# XOR.net
KiCad netlist of a schematic drawn in EAGLE
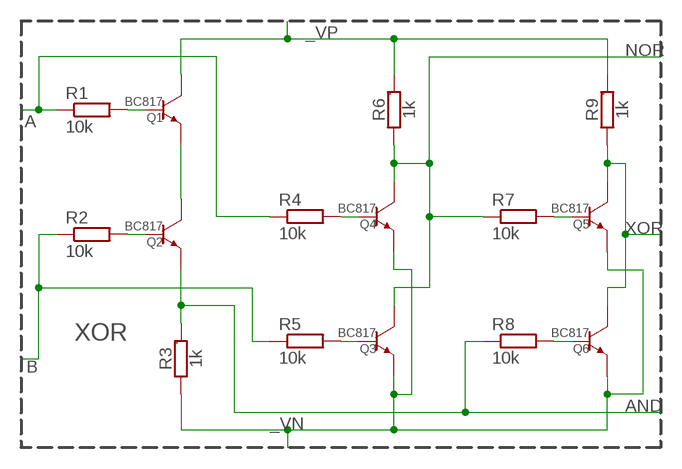
[diagram p0: schematic, sheet 1]

(export (version "E")
  (design (tool "Eeschema 10.0.6"))
  (components
    (comp (ref "Q1")
      (value "BC817")
      (footprint "eagle-import:SOT23")
      (libsource (lib "eagle-import") (part "TRANSISTOR-NPN-GENERIC-SOT23-BECDEFAULT"))
    )
    (comp (ref "Q2")
      (value "BC817")
      (footprint "eagle-import:SOT23")
      (libsource (lib "eagle-import") (part "TRANSISTOR-NPN-GENERIC-SOT23-BECDEFAULT"))
    )
    (comp (ref "Q3")
      (value "BC817")
      (footprint "eagle-import:SOT23")
      (libsource (lib "eagle-import") (part "TRANSISTOR-NPN-GENERIC-SOT23-BECDEFAULT"))
    )
    (comp (ref "Q4")
      (value "BC817")
      (footprint "eagle-import:SOT23")
      (libsource (lib "eagle-import") (part "TRANSISTOR-NPN-GENERIC-SOT23-BECDEFAULT"))
    )
    (comp (ref "Q5")
      (value "BC817")
      (footprint "eagle-import:SOT23")
      (libsource (lib "eagle-import") (part "TRANSISTOR-NPN-GENERIC-SOT23-BECDEFAULT"))
    )
    (comp (ref "Q6")
      (value "BC817")
      (footprint "eagle-import:SOT23")
      (libsource (lib "eagle-import") (part "TRANSISTOR-NPN-GENERIC-SOT23-BECDEFAULT"))
    )
    (comp (ref "R1")
      (value "10k")
      (footprint "eagle-import:R0603")
      (libsource (lib "eagle-import") (part "R-EU_R0603"))
    )
    (comp (ref "R2")
      (value "10k")
      (footprint "eagle-import:R0603")
      (libsource (lib "eagle-import") (part "R-EU_R0603"))
    )
    (comp (ref "R3")
      (value "1k")
      (footprint "eagle-import:R0603-MARK")
      (libsource (lib "eagle-import") (part "R-EU-MARKEDR0603"))
    )
    (comp (ref "R4")
      (value "10k")
      (footprint "eagle-import:R0603")
      (libsource (lib "eagle-import") (part "R-EU_R0603"))
    )
    (comp (ref "R5")
      (value "10k")
      (footprint "eagle-import:R0603")
      (libsource (lib "eagle-import") (part "R-EU_R0603"))
    )
    (comp (ref "R6")
      (value "1k")
      (footprint "eagle-import:R0603-MARK")
      (libsource (lib "eagle-import") (part "R-EU-MARKEDR0603"))
    )
    (comp (ref "R7")
      (value "10k")
      (footprint "eagle-import:R0603")
      (libsource (lib "eagle-import") (part "R-EU_R0603"))
    )
    (comp (ref "R8")
      (value "10k")
      (footprint "eagle-import:R0603")
      (libsource (lib "eagle-import") (part "R-EU_R0603"))
    )
    (comp (ref "R9")
      (value "1k")
      (footprint "eagle-import:R0603-MARK")
      (libsource (lib "eagle-import") (part "R-EU-MARKEDR0603"))
    )
  )
  (nets
    (net (code "1") (name "/A") (class "Default")
      (node (ref "R1") (pin "1") (pinfunction "1_1") (pintype "passive"))
      (node (ref "R4") (pin "1") (pinfunction "1_1") (pintype "passive"))
    )
    (net (code "2") (name "/AND") (class "Default")
      (node (ref "Q2") (pin "P$2") (pinfunction "EMITTER_P$2") (pintype "bidirectional"))
      (node (ref "R3") (pin "2") (pinfunction "2_2") (pintype "passive"))
      (node (ref "R8") (pin "1") (pinfunction "1_1") (pintype "passive"))
    )
    (net (code "3") (name "/B") (class "Default")
      (node (ref "R2") (pin "1") (pinfunction "1_1") (pintype "passive"))
      (node (ref "R5") (pin "1") (pinfunction "1_1") (pintype "passive"))
    )
    (net (code "4") (name "/NOR") (class "Default")
      (node (ref "Q3") (pin "P$3") (pinfunction "COLLECTOR_P$3") (pintype "bidirectional"))
      (node (ref "Q4") (pin "P$3") (pinfunction "COLLECTOR_P$3") (pintype "bidirectional"))
      (node (ref "R6") (pin "1") (pinfunction "1_1") (pintype "passive"))
      (node (ref "R7") (pin "1") (pinfunction "1_1") (pintype "passive"))
    )
    (net (code "5") (name "/XOR") (class "Default")
      (node (ref "Q5") (pin "P$3") (pinfunction "COLLECTOR_P$3") (pintype "bidirectional"))
      (node (ref "Q6") (pin "P$3") (pinfunction "COLLECTOR_P$3") (pintype "bidirectional"))
      (node (ref "R9") (pin "1") (pinfunction "1_1") (pintype "passive"))
    )
    (net (code "6") (name "/_VN") (class "Default")
      (node (ref "Q3") (pin "P$2") (pinfunction "EMITTER_P$2") (pintype "bidirectional"))
      (node (ref "Q4") (pin "P$2") (pinfunction "EMITTER_P$2") (pintype "bidirectional"))
      (node (ref "Q5") (pin "P$2") (pinfunction "EMITTER_P$2") (pintype "bidirectional"))
      (node (ref "Q6") (pin "P$2") (pinfunction "EMITTER_P$2") (pintype "bidirectional"))
      (node (ref "R3") (pin "1") (pinfunction "1_1") (pintype "passive"))
    )
    (net (code "7") (name "/_VP") (class "Default")
      (node (ref "Q1") (pin "P$3") (pinfunction "COLLECTOR_P$3") (pintype "bidirectional"))
      (node (ref "R6") (pin "2") (pinfunction "2_2") (pintype "passive"))
      (node (ref "R9") (pin "2") (pinfunction "2_2") (pintype "passive"))
    )
    (net (code "8") (name "Net-(Q1-BASE)") (class "Default")
      (node (ref "Q1") (pin "P$1") (pinfunction "BASE_P$1") (pintype "bidirectional"))
      (node (ref "R1") (pin "2") (pinfunction "2_2") (pintype "passive"))
    )
    (net (code "9") (name "Net-(Q1-EMITTER)") (class "Default")
      (node (ref "Q1") (pin "P$2") (pinfunction "EMITTER_P$2") (pintype "bidirectional"))
      (node (ref "Q2") (pin "P$3") (pinfunction "COLLECTOR_P$3") (pintype "bidirectional"))
    )
    (net (code "10") (name "Net-(Q2-BASE)") (class "Default")
      (node (ref "Q2") (pin "P$1") (pinfunction "BASE_P$1") (pintype "bidirectional"))
      (node (ref "R2") (pin "2") (pinfunction "2_2") (pintype "passive"))
    )
    (net (code "11") (name "Net-(Q3-BASE)") (class "Default")
      (node (ref "Q3") (pin "P$1") (pinfunction "BASE_P$1") (pintype "bidirectional"))
      (node (ref "R5") (pin "2") (pinfunction "2_2") (pintype "passive"))
    )
    (net (code "12") (name "Net-(Q4-BASE)") (class "Default")
      (node (ref "Q4") (pin "P$1") (pinfunction "BASE_P$1") (pintype "bidirectional"))
      (node (ref "R4") (pin "2") (pinfunction "2_2") (pintype "passive"))
    )
    (net (code "13") (name "Net-(Q5-BASE)") (class "Default")
      (node (ref "Q5") (pin "P$1") (pinfunction "BASE_P$1") (pintype "bidirectional"))
      (node (ref "R7") (pin "2") (pinfunction "2_2") (pintype "passive"))
    )
    (net (code "14") (name "Net-(Q6-BASE)") (class "Default")
      (node (ref "Q6") (pin "P$1") (pinfunction "BASE_P$1") (pintype "bidirectional"))
      (node (ref "R8") (pin "2") (pinfunction "2_2") (pintype "passive"))
    )
  )
)
